# emi_filter_ch0_a.net
KiCad netlist of a schematic drawn in Altium Designer
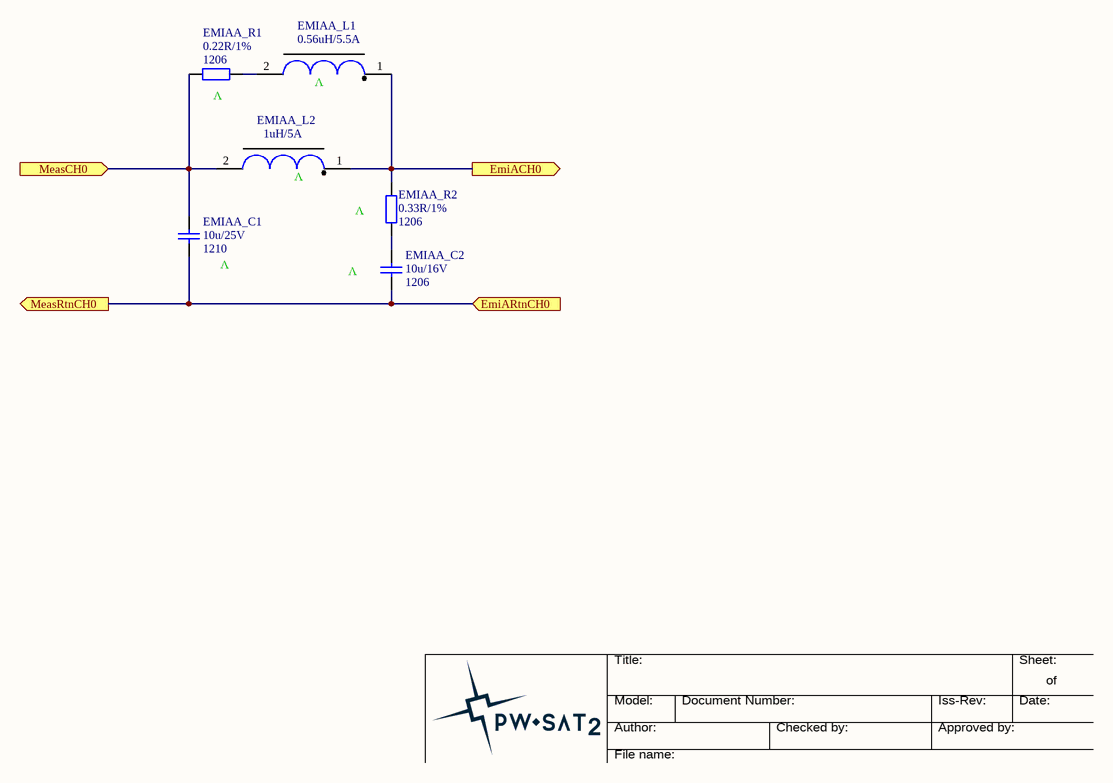
[diagram p0: emi_filter_ch0_a.SchDoc]

(export (version "E")
  (design (tool "Eeschema 10.0.6"))
  (components
    (comp (ref "EMIAA_C1")
      (value "10u/25V")
      (footprint "SMD_Capacitor_1210")
      (description "Ceramic Cap Murata Automotive 10u/25V X7R 1210")
      (fields
        (field (name "MANUFACTURER") "Murata")
        (field (name "MANUFACTURERPARTNUMBER") "GCJ32ER71E106KA12L")
        (field (name "PACKAGE") "1210")
      )
      (libsource (lib "capacitors") (part "Cer_GCJ32ER71E106KA12L"))
    )
    (comp (ref "EMIAA_C2")
      (value "10u/16V")
      (footprint "SMD_Capacitor_1206")
      (description "Ceramic Cap Kemet COTS 10u/16V X7R 1206")
      (fields
        (field (name "MANUFACTURERPARTNUMBER") "C1206T106K4RACTU")
        (field (name "MANUFACTURER") "Kemet")
        (field (name "PACKGE") "1206")
      )
      (libsource (lib "capacitors") (part "Cer_C1206T106K4RACTU"))
    )
    (comp (ref "EMIAA_L1")
      (value "0.56uH/5.5A")
      (footprint "Vishay_IHLP1212")
      (description "Vishay IHLP1212 Inductor, L=0.56uH, Irise40deg=5.5A, ESR=16mR, SRF=1MHz.")
      (fields
        (field (name "MANUFACTURER") "Vishay")
        (field (name "MANUFACTURERPARTNUMBER") "IHLP1212BZERR56M11")
      )
      (libsource (lib "inductors") (part "IHLP1212BZERR56M11"))
    )
    (comp (ref "EMIAA_L2")
      (value "1uH/5A")
      (footprint "Vishay_IHLP1212")
      (description "Vishay IHLP1212 Inductor, L=1uH, Irise40deg=5A, ESR=20mR, SRF=1MHz.")
      (fields
        (field (name "MANUFACTURER") "Vishay")
        (field (name "MANUFACTURERPARTNUMBER") "IHLP1212BZER1R0M11")
      )
      (libsource (lib "inductors") (part "IHLP1212BZER1R0M11"))
    )
    (comp (ref "EMIAA_R1")
      (value "0.22R/1%")
      (footprint "SMD_Resistor_1206")
      (description "Panasonic Resistor 0.22R 1% 1206 330mW")
      (fields
        (field (name "MANUFACTURER") "Panasonic")
        (field (name "MANUFACTURERPARTNUMBER") "ERJ-8BQFR22V")
        (field (name "PACKAGE") "1206")
      )
      (libsource (lib "resistors") (part "ERJ-8BQFR22V"))
    )
    (comp (ref "EMIAA_R2")
      (value "0.33R/1%")
      (footprint "SMD_Resistor_1206")
      (description "Panasonic Resistor 0.33R 1% 1206 330mW")
      (fields
        (field (name "MANUFACTURER") "Panasonic")
        (field (name "MANUFACTURERPARTNUMBER") "ERJ-8BQFR33V")
        (field (name "PACKAGE") "1206")
      )
      (libsource (lib "resistors") (part "ERJ-8BQFR33V"))
    )
  )
  (nets
    (net (code "1") (name "/EmiACH0") (class "Default")
      (node (ref "EMIAA_L1") (pin "1") (pinfunction "1_1") (pintype "passive"))
      (node (ref "EMIAA_L2") (pin "1") (pinfunction "1_1") (pintype "passive"))
      (node (ref "EMIAA_R2") (pin "2") (pinfunction "2_2") (pintype "passive"))
    )
    (net (code "2") (name "/EmiARtnCH0") (class "Default")
      (node (ref "EMIAA_C1") (pin "2") (pinfunction "2_2") (pintype "passive"))
      (node (ref "EMIAA_C2") (pin "2") (pinfunction "2_2") (pintype "passive"))
    )
    (net (code "3") (name "/MeasCH0") (class "Default")
      (node (ref "EMIAA_C1") (pin "1") (pinfunction "1_1") (pintype "passive"))
      (node (ref "EMIAA_L2") (pin "2") (pinfunction "2_2") (pintype "passive"))
      (node (ref "EMIAA_R1") (pin "1") (pinfunction "1_1") (pintype "passive"))
    )
    (net (code "4") (name "Net-(EMIAA_C2-Pad1)") (class "Default")
      (node (ref "EMIAA_C2") (pin "1") (pinfunction "1_1") (pintype "passive"))
      (node (ref "EMIAA_R2") (pin "1") (pinfunction "1_1") (pintype "passive"))
    )
    (net (code "5") (name "Net-(EMIAA_L1-Pad2)") (class "Default")
      (node (ref "EMIAA_L1") (pin "2") (pinfunction "2_2") (pintype "passive"))
      (node (ref "EMIAA_R1") (pin "2") (pinfunction "2_2") (pintype "passive"))
    )
  )
)
